# RightSideIoConnectors.net
KiCad netlist of a schematic drawn in EAGLE
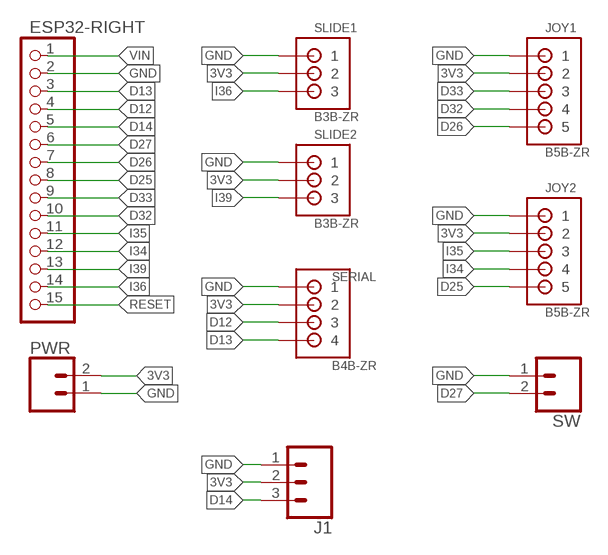
[diagram p0: schematic, sheet 1]

(export (version "E")
  (design (tool "Eeschema 10.0.6"))
  (components
    (comp (ref "ESP32-RIGHT")
      (value "0")
      (footprint "eagle-import:1X15")
      (libsource (lib "eagle-import") (part "PINHD-1X15"))
    )
    (comp (ref "J1")
      (value "CONN_03")
      (footprint "eagle-import:1X03")
      (libsource (lib "eagle-import") (part "CONN_03"))
    )
    (comp (ref "JOY1")
      (value "B5B-ZR")
      (footprint "eagle-import:B5B-ZR")
      (libsource (lib "eagle-import") (part "B5B-ZR"))
    )
    (comp (ref "JOY2")
      (value "B5B-ZR")
      (footprint "eagle-import:B5B-ZR")
      (libsource (lib "eagle-import") (part "B5B-ZR"))
    )
    (comp (ref "PWR")
      (value "CONN_02")
      (footprint "eagle-import:1X02")
      (libsource (lib "eagle-import") (part "CONN_02"))
    )
    (comp (ref "SERIAL")
      (value "B4B-ZR")
      (footprint "eagle-import:B4B-ZR")
      (libsource (lib "eagle-import") (part "B4B-ZR"))
    )
    (comp (ref "SLIDE1")
      (value "B3B-ZR")
      (footprint "eagle-import:B3B-ZR")
      (libsource (lib "eagle-import") (part "B3B-ZR"))
    )
    (comp (ref "SLIDE2")
      (value "B3B-ZR")
      (footprint "eagle-import:B3B-ZR")
      (libsource (lib "eagle-import") (part "B3B-ZR"))
    )
    (comp (ref "SW")
      (value "CONN_02")
      (footprint "eagle-import:1X02")
      (libsource (lib "eagle-import") (part "CONN_02"))
    )
  )
  (nets
    (net (code "1") (name "3V3") (class "Default")
      (node (ref "J1") (pin "2") (pinfunction "2_2") (pintype "passive"))
      (node (ref "JOY1") (pin "2") (pinfunction "2_2") (pintype "bidirectional"))
      (node (ref "JOY2") (pin "2") (pinfunction "2_2") (pintype "bidirectional"))
      (node (ref "PWR") (pin "2") (pinfunction "2_2") (pintype "passive"))
      (node (ref "SERIAL") (pin "2") (pinfunction "2_2") (pintype "bidirectional"))
      (node (ref "SLIDE1") (pin "2") (pinfunction "2_2") (pintype "bidirectional"))
      (node (ref "SLIDE2") (pin "2") (pinfunction "2_2") (pintype "bidirectional"))
    )
    (net (code "2") (name "D12") (class "Default")
      (node (ref "ESP32-RIGHT") (pin "4") (pinfunction "4_4") (pintype "passive"))
      (node (ref "SERIAL") (pin "3") (pinfunction "3_3") (pintype "bidirectional"))
    )
    (net (code "3") (name "D13") (class "Default")
      (node (ref "ESP32-RIGHT") (pin "3") (pinfunction "3_3") (pintype "passive"))
      (node (ref "SERIAL") (pin "4") (pinfunction "4_4") (pintype "bidirectional"))
    )
    (net (code "4") (name "D14") (class "Default")
      (node (ref "ESP32-RIGHT") (pin "5") (pinfunction "5_5") (pintype "passive"))
      (node (ref "J1") (pin "3") (pinfunction "3_3") (pintype "passive"))
    )
    (net (code "5") (name "D25") (class "Default")
      (node (ref "ESP32-RIGHT") (pin "8") (pinfunction "8_8") (pintype "passive"))
      (node (ref "JOY2") (pin "5") (pinfunction "5_5") (pintype "bidirectional"))
    )
    (net (code "6") (name "D26") (class "Default")
      (node (ref "ESP32-RIGHT") (pin "7") (pinfunction "7_7") (pintype "passive"))
      (node (ref "JOY1") (pin "5") (pinfunction "5_5") (pintype "bidirectional"))
    )
    (net (code "7") (name "D27") (class "Default")
      (node (ref "ESP32-RIGHT") (pin "6") (pinfunction "6_6") (pintype "passive"))
      (node (ref "SW") (pin "2") (pinfunction "2_2") (pintype "passive"))
    )
    (net (code "8") (name "D32") (class "Default")
      (node (ref "ESP32-RIGHT") (pin "10") (pinfunction "10_10") (pintype "passive"))
      (node (ref "JOY1") (pin "4") (pinfunction "4_4") (pintype "bidirectional"))
    )
    (net (code "9") (name "D33") (class "Default")
      (node (ref "ESP32-RIGHT") (pin "9") (pinfunction "9_9") (pintype "passive"))
      (node (ref "JOY1") (pin "3") (pinfunction "3_3") (pintype "bidirectional"))
    )
    (net (code "10") (name "GND") (class "Default")
      (node (ref "ESP32-RIGHT") (pin "2") (pinfunction "2_2") (pintype "passive"))
      (node (ref "J1") (pin "1") (pinfunction "1_1") (pintype "passive"))
      (node (ref "JOY1") (pin "1") (pinfunction "1_1") (pintype "bidirectional"))
      (node (ref "JOY2") (pin "1") (pinfunction "1_1") (pintype "bidirectional"))
      (node (ref "PWR") (pin "1") (pinfunction "1_1") (pintype "passive"))
      (node (ref "SERIAL") (pin "1") (pinfunction "1_1") (pintype "bidirectional"))
      (node (ref "SLIDE1") (pin "1") (pinfunction "1_1") (pintype "bidirectional"))
      (node (ref "SLIDE2") (pin "1") (pinfunction "1_1") (pintype "bidirectional"))
      (node (ref "SW") (pin "1") (pinfunction "1_1") (pintype "passive"))
    )
    (net (code "11") (name "I34") (class "Default")
      (node (ref "ESP32-RIGHT") (pin "12") (pinfunction "12_12") (pintype "passive"))
      (node (ref "JOY2") (pin "4") (pinfunction "4_4") (pintype "bidirectional"))
    )
    (net (code "12") (name "I35") (class "Default")
      (node (ref "ESP32-RIGHT") (pin "11") (pinfunction "11_11") (pintype "passive"))
      (node (ref "JOY2") (pin "3") (pinfunction "3_3") (pintype "bidirectional"))
    )
    (net (code "13") (name "I36") (class "Default")
      (node (ref "ESP32-RIGHT") (pin "14") (pinfunction "14_14") (pintype "passive"))
      (node (ref "SLIDE1") (pin "3") (pinfunction "3_3") (pintype "bidirectional"))
    )
    (net (code "14") (name "I39") (class "Default")
      (node (ref "ESP32-RIGHT") (pin "13") (pinfunction "13_13") (pintype "passive"))
      (node (ref "SLIDE2") (pin "3") (pinfunction "3_3") (pintype "bidirectional"))
    )
    (net (code "15") (name "RESET") (class "Default")
      (node (ref "ESP32-RIGHT") (pin "15") (pinfunction "15_15") (pintype "passive"))
    )
    (net (code "16") (name "VIN") (class "Default")
      (node (ref "ESP32-RIGHT") (pin "1") (pinfunction "1_1") (pintype "passive"))
    )
  )
)
